# SPI_breaktout_to_HDMI.net
KiCad netlist of a schematic drawn in Altium Designer
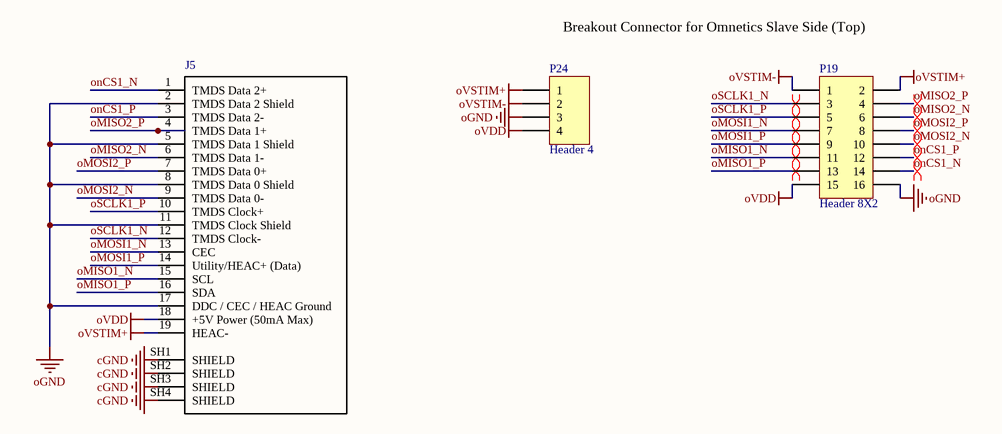
[diagram p0: SPI_breaktout_to_HDMI.SchDoc]

(export (version "E")
  (design (tool "Eeschema 10.0.6"))
  (components
    (comp (ref "J5")
      (value "1747981-2")
      (footprint "te_connectivity_audio_video_connectors:TE_1747981-2_1747981-2(Primary)")
      (description "Conn HDMI RCP 19 POS 0.5mm Solder ST SMD 19 Terminal 1 Port T/R")
      (fields (field (name "MF") "TE Connectivity"))
      (libsource (lib "te_connectivity_audio_video_connectors") (part "1747981-2"))
    )
    (comp (ref "P19")
      (value "Header 8X2")
      (footprint "te_connectivity_headers:TE_534998-8")
      (description "Header, 8-Pin, Dual row")
      (fields
        (field (name "MANUFACTURER") "TE Connectivity")
        (field (name "MANUFACTURER PART NUMBER") "534998-8")
        (field (name "PUBLISHER") "Altium Limited")
      )
      (libsource (lib "Miscellaneous Connectors") (part "Header 8X2"))
    )
    (comp (ref "P24")
      (value "Header 4")
      (footprint "on_shore_rising_clamp:OSTVN04A150")
      (description "Header, 4-Pin")
      (fields
        (field (name "MANUFACTURER") "On Shore Technology Inc.")
        (field (name "MANUFACTURER PART NUMBER") "OSTVN04A150")
        (field (name "PUBLISHER") "Altium Limited")
      )
      (libsource (lib "standard_components") (part "Header 4"))
    )
  )
  (nets
    (net (code "1") (name "/oMISO1_N") (class "Default")
      (node (ref "J5") (pin "15") (pinfunction "SCL_15") (pintype "passive"))
      (node (ref "P19") (pin "11") (pinfunction "11_11") (pintype "passive"))
    )
    (net (code "2") (name "/oMISO1_P") (class "Default")
      (node (ref "J5") (pin "16") (pinfunction "SDA_16") (pintype "passive"))
      (node (ref "P19") (pin "13") (pinfunction "13_13") (pintype "passive"))
    )
    (net (code "3") (name "/oMISO2_N") (class "Default")
      (node (ref "J5") (pin "6") (pinfunction "TMDS_Data_1-_6") (pintype "passive"))
      (node (ref "P19") (pin "6") (pinfunction "6_6") (pintype "passive"))
    )
    (net (code "4") (name "/oMISO2_P") (class "Default")
      (node (ref "J5") (pin "4") (pinfunction "TMDS_Data_1+_4") (pintype "passive"))
      (node (ref "P19") (pin "4") (pinfunction "4_4") (pintype "passive"))
    )
    (net (code "5") (name "/oMOSI1_N") (class "Default")
      (node (ref "J5") (pin "13") (pinfunction "CEC_13") (pintype "passive"))
      (node (ref "P19") (pin "7") (pinfunction "7_7") (pintype "passive"))
    )
    (net (code "6") (name "/oMOSI1_P") (class "Default")
      (node (ref "J5") (pin "14") (pinfunction "Utility/HEAC+_(Data)_14") (pintype "passive"))
      (node (ref "P19") (pin "9") (pinfunction "9_9") (pintype "passive"))
    )
    (net (code "7") (name "/oMOSI2_N") (class "Default")
      (node (ref "J5") (pin "9") (pinfunction "TMDS_Data_0-_9") (pintype "passive"))
      (node (ref "P19") (pin "10") (pinfunction "10_10") (pintype "passive"))
    )
    (net (code "8") (name "/oMOSI2_P") (class "Default")
      (node (ref "J5") (pin "7") (pinfunction "TMDS_Data_0+_7") (pintype "passive"))
      (node (ref "P19") (pin "8") (pinfunction "8_8") (pintype "passive"))
    )
    (net (code "9") (name "/oSCLK1_N") (class "Default")
      (node (ref "J5") (pin "12") (pinfunction "TMDS_Clock-_12") (pintype "passive"))
      (node (ref "P19") (pin "3") (pinfunction "3_3") (pintype "passive"))
    )
    (net (code "10") (name "/oSCLK1_P") (class "Default")
      (node (ref "J5") (pin "10") (pinfunction "TMDS_Clock+_10") (pintype "passive"))
      (node (ref "P19") (pin "5") (pinfunction "5_5") (pintype "passive"))
    )
    (net (code "11") (name "/onCS1_N") (class "Default")
      (node (ref "J5") (pin "1") (pinfunction "TMDS_Data_2+_1") (pintype "passive"))
      (node (ref "P19") (pin "14") (pinfunction "14_14") (pintype "passive"))
    )
    (net (code "12") (name "/onCS1_P") (class "Default")
      (node (ref "J5") (pin "3") (pinfunction "TMDS_Data_2-_3") (pintype "passive"))
      (node (ref "P19") (pin "12") (pinfunction "12_12") (pintype "passive"))
    )
    (net (code "13") (name "cGND") (class "Default")
      (node (ref "J5") (pin "SH1") (pinfunction "SHIELD_SH1") (pintype "passive"))
      (node (ref "J5") (pin "SH2") (pinfunction "SHIELD_SH2") (pintype "passive"))
      (node (ref "J5") (pin "SH3") (pinfunction "SHIELD_SH3") (pintype "passive"))
      (node (ref "J5") (pin "SH4") (pinfunction "SHIELD_SH4") (pintype "passive"))
    )
    (net (code "14") (name "oGND") (class "Default")
      (node (ref "J5") (pin "11") (pinfunction "TMDS_Clock_Shield_11") (pintype "passive"))
      (node (ref "J5") (pin "17") (pinfunction "DDC_/_CEC_/_HEAC_Ground_17") (pintype "passive"))
      (node (ref "J5") (pin "2") (pinfunction "TMDS_Data_2_Shield_2") (pintype "passive"))
      (node (ref "J5") (pin "5") (pinfunction "TMDS_Data_1_Shield_5") (pintype "passive"))
      (node (ref "J5") (pin "8") (pinfunction "TMDS_Data_0_Shield_8") (pintype "passive"))
      (node (ref "P19") (pin "16") (pinfunction "16_16") (pintype "passive"))
      (node (ref "P24") (pin "3") (pinfunction "3_3") (pintype "passive"))
    )
    (net (code "15") (name "oVDD") (class "Default")
      (node (ref "J5") (pin "18") (pinfunction "+5V_Power_(50mA_Max)_18") (pintype "passive"))
      (node (ref "P19") (pin "15") (pinfunction "15_15") (pintype "passive"))
      (node (ref "P24") (pin "4") (pinfunction "4_4") (pintype "passive"))
    )
    (net (code "16") (name "oVSTIM+") (class "Default")
      (node (ref "J5") (pin "19") (pinfunction "HEAC-_19") (pintype "passive"))
      (node (ref "P19") (pin "2") (pinfunction "2_2") (pintype "passive"))
      (node (ref "P24") (pin "1") (pinfunction "1_1") (pintype "passive"))
    )
    (net (code "17") (name "oVSTIM-") (class "Default")
      (node (ref "P19") (pin "1") (pinfunction "1_1") (pintype "passive"))
      (node (ref "P24") (pin "2") (pinfunction "2_2") (pintype "passive"))
    )
  )
)
